# Notch-Filter-1.net
KiCad netlist of a schematic drawn in Altium Designer
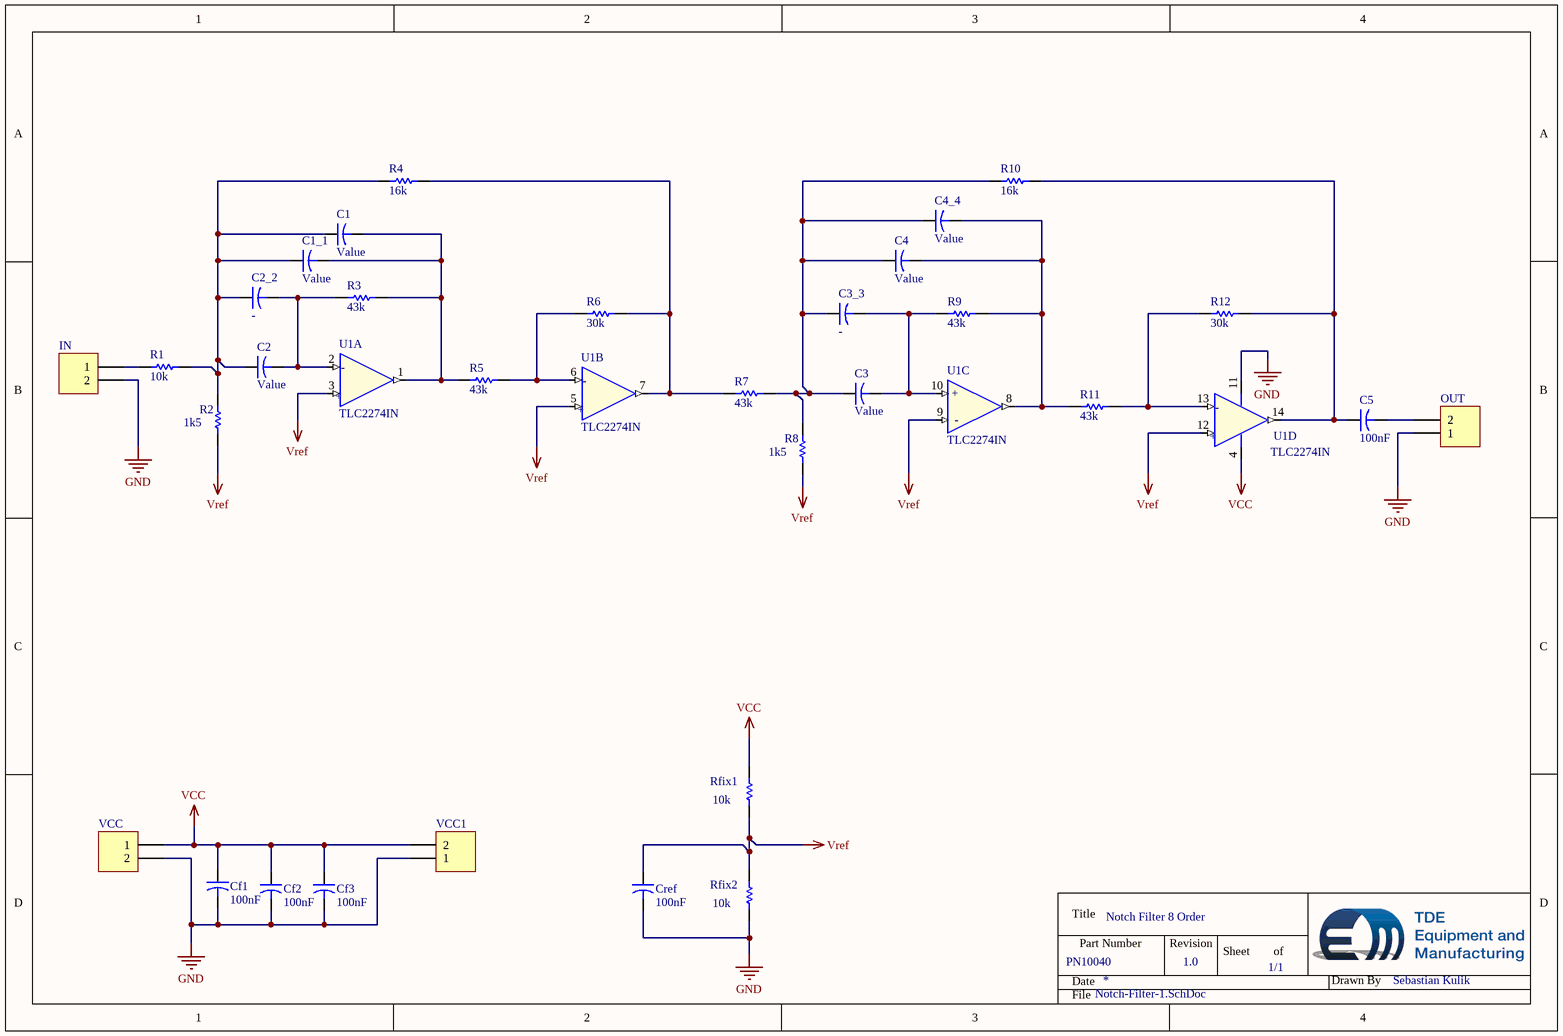
[diagram p0: Notch-Filter-1.SchDoc]

(export (version "E")
  (design (tool "Eeschema 10.0.6"))
  (components
    (comp (ref "C1")
      (value "Value")
      (footprint "Dummy-10mm")
      (description "Capacitor-Dummy-THT")
      (fields (field (name "PUBLISHER") "Sebastian Kulik"))
      (libsource (lib "Capacitors") (part "Capacitor-Dummy-THT"))
    )
    (comp (ref "C1_1")
      (value "Value")
      (footprint "Dummy-10mm")
      (description "Capacitor-Dummy-THT")
      (fields (field (name "PUBLISHER") "Sebastian Kulik"))
      (libsource (lib "Capacitors") (part "Capacitor-Dummy-THT"))
    )
    (comp (ref "C2")
      (value "Value")
      (footprint "Dummy-10mm")
      (description "Capacitor-Dummy-THT")
      (fields (field (name "PUBLISHER") "Sebastian Kulik"))
      (libsource (lib "Capacitors") (part "Capacitor-Dummy-THT"))
    )
    (comp (ref "C2_2")
      (value "-")
      (footprint "Dummy-10mm")
      (description "Capacitor-Dummy-THT")
      (fields (field (name "PUBLISHER") "Sebastian Kulik"))
      (libsource (lib "Capacitors") (part "Capacitor-Dummy-THT"))
    )
    (comp (ref "C3")
      (value "Value")
      (footprint "Dummy-10mm")
      (description "Capacitor-Dummy-THT")
      (fields (field (name "PUBLISHER") "Sebastian Kulik"))
      (libsource (lib "Capacitors") (part "Capacitor-Dummy-THT"))
    )
    (comp (ref "C3_3")
      (value "-")
      (footprint "Dummy-10mm")
      (description "Capacitor-Dummy-THT")
      (fields (field (name "PUBLISHER") "Sebastian Kulik"))
      (libsource (lib "Capacitors") (part "Capacitor-Dummy-THT"))
    )
    (comp (ref "C4")
      (value "Value")
      (footprint "Dummy-10mm")
      (description "Capacitor-Dummy-THT")
      (fields (field (name "PUBLISHER") "Sebastian Kulik"))
      (libsource (lib "Capacitors") (part "Capacitor-Dummy-THT"))
    )
    (comp (ref "C4_4")
      (value "Value")
      (footprint "Dummy-10mm")
      (description "Capacitor-Dummy-THT")
      (fields (field (name "PUBLISHER") "Sebastian Kulik"))
      (libsource (lib "Capacitors") (part "Capacitor-Dummy-THT"))
    )
    (comp (ref "C5")
      (value "100nF")
      (footprint "Dummy-10mm")
      (description "Capacitor-Dummy-THT")
      (fields (field (name "PUBLISHER") "Sebastian Kulik"))
      (libsource (lib "Capacitors") (part "Capacitor-Dummy-THT"))
    )
    (comp (ref "Cf1")
      (value "100nF")
      (footprint "Dummy-10mm")
      (description "Capacitor-Dummy-THT")
      (fields (field (name "PUBLISHER") "Sebastian Kulik"))
      (libsource (lib "Capacitors") (part "Capacitor-Dummy-THT"))
    )
    (comp (ref "Cf2")
      (value "100nF")
      (footprint "Dummy-10mm")
      (description "Capacitor-Dummy-THT")
      (fields (field (name "PUBLISHER") "Sebastian Kulik"))
      (libsource (lib "Capacitors") (part "Capacitor-Dummy-THT"))
    )
    (comp (ref "Cf3")
      (value "100nF")
      (footprint "Dummy-10mm")
      (description "Capacitor-Dummy-THT")
      (fields (field (name "PUBLISHER") "Sebastian Kulik"))
      (libsource (lib "Capacitors") (part "Capacitor-Dummy-THT"))
    )
    (comp (ref "Cref")
      (value "100nF")
      (footprint "Dummy-10mm")
      (description "Capacitor-Dummy-THT")
      (fields (field (name "PUBLISHER") "Sebastian Kulik"))
      (libsource (lib "Capacitors") (part "Capacitor-Dummy-THT"))
    )
    (comp (ref "IN")
      (value "PHOENIX_1715721")
      (footprint "Phoenix-2-5_08")
      (description "Phoenix, 2 pol, 5.08mm, 22A, 715721")
      (fields (field (name "MANUFACTURER") "Phoenix") (field (name "PUBLISHER") "Sebastian Kulik"))
      (libsource (lib "") (part "2Pol_1715721_1"))
    )
    (comp (ref "OUT")
      (value "PHOENIX_1715721")
      (footprint "Phoenix-2-5_08")
      (description "Phoenix, 2 pol, 5.08mm, 22A, 715721")
      (fields (field (name "MANUFACTURER") "Phoenix") (field (name "PUBLISHER") "Sebastian Kulik"))
      (libsource (lib "Connectors") (part "2Pol_1715721"))
    )
    (comp (ref "R1")
      (value "10k")
      (footprint "Dummy-10mm")
      (description "Resistor-Dummy-THT")
      (fields (field (name "PUBLISHER") "Sebastian Kulik"))
      (libsource (lib "Resistors") (part "Resistor-Dummy-THT"))
    )
    (comp (ref "R2")
      (value "1k5")
      (footprint "Dummy-10mm")
      (description "Resistor-Dummy-THT")
      (fields (field (name "PUBLISHER") "Sebastian Kulik"))
      (libsource (lib "Resistors") (part "Resistor-Dummy-THT"))
    )
    (comp (ref "R3")
      (value "43k")
      (footprint "Dummy-10mm")
      (description "Resistor-Dummy-THT")
      (fields (field (name "PUBLISHER") "Sebastian Kulik"))
      (libsource (lib "Resistors") (part "Resistor-Dummy-THT"))
    )
    (comp (ref "R4")
      (value "16k")
      (footprint "Dummy-10mm")
      (description "Resistor-Dummy-THT")
      (fields (field (name "PUBLISHER") "Sebastian Kulik"))
      (libsource (lib "Resistors") (part "Resistor-Dummy-THT"))
    )
    (comp (ref "R5")
      (value "43k")
      (footprint "Dummy-10mm")
      (description "Resistor-Dummy-THT")
      (fields (field (name "PUBLISHER") "Sebastian Kulik"))
      (libsource (lib "Resistors") (part "Resistor-Dummy-THT"))
    )
    (comp (ref "R6")
      (value "30k")
      (footprint "Dummy-10mm")
      (description "Resistor-Dummy-THT")
      (fields (field (name "PUBLISHER") "Sebastian Kulik"))
      (libsource (lib "Resistors") (part "Resistor-Dummy-THT"))
    )
    (comp (ref "R7")
      (value "43k")
      (footprint "Dummy-10mm")
      (description "Resistor-Dummy-THT")
      (fields (field (name "PUBLISHER") "Sebastian Kulik"))
      (libsource (lib "Resistors") (part "Resistor-Dummy-THT"))
    )
    (comp (ref "R8")
      (value "1k5")
      (footprint "Dummy-10mm")
      (description "Resistor-Dummy-THT")
      (fields (field (name "PUBLISHER") "Sebastian Kulik"))
      (libsource (lib "Resistors") (part "Resistor-Dummy-THT"))
    )
    (comp (ref "R9")
      (value "43k")
      (footprint "Dummy-10mm")
      (description "Resistor-Dummy-THT")
      (fields (field (name "PUBLISHER") "Sebastian Kulik"))
      (libsource (lib "Resistors") (part "Resistor-Dummy-THT"))
    )
    (comp (ref "R10")
      (value "16k")
      (footprint "Dummy-10mm")
      (description "Resistor-Dummy-THT")
      (fields (field (name "PUBLISHER") "Sebastian Kulik"))
      (libsource (lib "Resistors") (part "Resistor-Dummy-THT"))
    )
    (comp (ref "R11")
      (value "43k")
      (footprint "Dummy-10mm")
      (description "Resistor-Dummy-THT")
      (fields (field (name "PUBLISHER") "Sebastian Kulik"))
      (libsource (lib "Resistors") (part "Resistor-Dummy-THT"))
    )
    (comp (ref "R12")
      (value "30k")
      (footprint "Dummy-10mm")
      (description "Resistor-Dummy-THT")
      (fields (field (name "PUBLISHER") "Sebastian Kulik"))
      (libsource (lib "Resistors") (part "Resistor-Dummy-THT"))
    )
    (comp (ref "Rfix1")
      (value "10k")
      (footprint "Dummy-10mm")
      (description "Resistor-Dummy-THT")
      (fields (field (name "PUBLISHER") "Sebastian Kulik"))
      (libsource (lib "Resistors") (part "Resistor-Dummy-THT"))
    )
    (comp (ref "Rfix2")
      (value "10k")
      (footprint "Dummy-10mm")
      (description "Resistor-Dummy-THT")
      (fields (field (name "PUBLISHER") "Sebastian Kulik"))
      (libsource (lib "Resistors") (part "Resistor-Dummy-THT"))
    )
    (comp (ref "U1")
      (value "TLC2274IN")
      (footprint "DIP-14")
      (description "Reel to Reel  quad OP")
      (fields (field (name "MANUFACTURER") "TI") (field (name "PUBLISHER") "Sebastian Kulik"))
      (libsource (lib "ICs") (part "TLC2274IN"))
    )
    (comp (ref "VCC")
      (value "PHOENIX_1715721")
      (footprint "Phoenix-2-5_08")
      (description "Phoenix, 2 pol, 5.08mm, 22A, 715721")
      (fields (field (name "MANUFACTURER") "Phoenix") (field (name "PUBLISHER") "Sebastian Kulik"))
      (libsource (lib "") (part "2Pol_1715721_1"))
    )
    (comp (ref "VCC1")
      (value "PHOENIX_1715721")
      (footprint "Phoenix-2-5_08")
      (description "Phoenix, 2 pol, 5.08mm, 22A, 715721")
      (fields (field (name "MANUFACTURER") "Phoenix") (field (name "PUBLISHER") "Sebastian Kulik"))
      (libsource (lib "Connectors") (part "2Pol_1715721"))
    )
  )
  (nets
    (net (code "1") (name "GND") (class "Default")
      (node (ref "Cf1") (pin "2") (pinfunction "2_2") (pintype "passive"))
      (node (ref "Cf2") (pin "2") (pinfunction "2_2") (pintype "passive"))
      (node (ref "Cf3") (pin "2") (pinfunction "2_2") (pintype "passive"))
      (node (ref "Cref") (pin "2") (pinfunction "2_2") (pintype "passive"))
      (node (ref "IN") (pin "2") (pinfunction "2_2") (pintype "passive"))
      (node (ref "OUT") (pin "1") (pinfunction "1_1") (pintype "passive"))
      (node (ref "Rfix2") (pin "1") (pinfunction "1_1") (pintype "passive"))
      (node (ref "U1") (pin "11") (pinfunction "V-_11") (pintype "power_in"))
      (node (ref "VCC") (pin "2") (pinfunction "2_2") (pintype "passive"))
      (node (ref "VCC1") (pin "1") (pinfunction "1_1") (pintype "passive"))
    )
    (net (code "2") (name "Net-(C1-Pad1)") (class "Default")
      (node (ref "C1") (pin "1") (pinfunction "1_1") (pintype "passive"))
      (node (ref "C1_1") (pin "1") (pinfunction "1_1") (pintype "passive"))
      (node (ref "C2") (pin "1") (pinfunction "1_1") (pintype "passive"))
      (node (ref "C2_2") (pin "1") (pinfunction "1_1") (pintype "passive"))
      (node (ref "R1") (pin "1") (pinfunction "1_1") (pintype "passive"))
      (node (ref "R2") (pin "2") (pinfunction "2_2") (pintype "passive"))
      (node (ref "R4") (pin "2") (pinfunction "2_2") (pintype "passive"))
    )
    (net (code "3") (name "Net-(C3-Pad1)") (class "Default")
      (node (ref "C3") (pin "1") (pinfunction "1_1") (pintype "passive"))
      (node (ref "C3_3") (pin "1") (pinfunction "1_1") (pintype "passive"))
      (node (ref "C4") (pin "1") (pinfunction "1_1") (pintype "passive"))
      (node (ref "C4_4") (pin "1") (pinfunction "1_1") (pintype "passive"))
      (node (ref "R10") (pin "2") (pinfunction "2_2") (pintype "passive"))
      (node (ref "R7") (pin "1") (pinfunction "1_1") (pintype "passive"))
      (node (ref "R8") (pin "2") (pinfunction "2_2") (pintype "passive"))
    )
    (net (code "4") (name "Net-(C5-Pad2)") (class "Default")
      (node (ref "C5") (pin "2") (pinfunction "2_2") (pintype "passive"))
      (node (ref "OUT") (pin "2") (pinfunction "2_2") (pintype "passive"))
    )
    (net (code "5") (name "Net-(IN-Pad1)") (class "Default")
      (node (ref "IN") (pin "1") (pinfunction "1_1") (pintype "passive"))
      (node (ref "R1") (pin "2") (pinfunction "2_2") (pintype "passive"))
    )
    (net (code "6") (name "Net-(U1A-IN+)") (class "Default")
      (node (ref "C2") (pin "2") (pinfunction "2_2") (pintype "passive"))
      (node (ref "C2_2") (pin "2") (pinfunction "2_2") (pintype "passive"))
      (node (ref "R3") (pin "1") (pinfunction "1_1") (pintype "passive"))
      (node (ref "U1") (pin "2") (pinfunction "IN+_2") (pintype "input"))
    )
    (net (code "7") (name "Net-(U1A-OUT)") (class "Default")
      (node (ref "C1") (pin "2") (pinfunction "2_2") (pintype "passive"))
      (node (ref "C1_1") (pin "2") (pinfunction "2_2") (pintype "passive"))
      (node (ref "R3") (pin "2") (pinfunction "2_2") (pintype "passive"))
      (node (ref "R5") (pin "1") (pinfunction "1_1") (pintype "passive"))
      (node (ref "U1") (pin "1") (pinfunction "OUT_1") (pintype "output"))
    )
    (net (code "8") (name "Net-(U1B-IN+)") (class "Default")
      (node (ref "R5") (pin "2") (pinfunction "2_2") (pintype "passive"))
      (node (ref "R6") (pin "1") (pinfunction "1_1") (pintype "passive"))
      (node (ref "U1") (pin "6") (pinfunction "IN+_6") (pintype "input"))
    )
    (net (code "9") (name "Net-(U1B-OUT)") (class "Default")
      (node (ref "R4") (pin "1") (pinfunction "1_1") (pintype "passive"))
      (node (ref "R6") (pin "2") (pinfunction "2_2") (pintype "passive"))
      (node (ref "R7") (pin "2") (pinfunction "2_2") (pintype "passive"))
      (node (ref "U1") (pin "7") (pinfunction "OUT_7") (pintype "output"))
    )
    (net (code "10") (name "Net-(U1C-IN-)") (class "Default")
      (node (ref "C3") (pin "2") (pinfunction "2_2") (pintype "passive"))
      (node (ref "C3_3") (pin "2") (pinfunction "2_2") (pintype "passive"))
      (node (ref "R9") (pin "2") (pinfunction "2_2") (pintype "passive"))
      (node (ref "U1") (pin "10") (pinfunction "IN-_10") (pintype "input"))
    )
    (net (code "11") (name "Net-(U1C-OUT)") (class "Default")
      (node (ref "C4") (pin "2") (pinfunction "2_2") (pintype "passive"))
      (node (ref "C4_4") (pin "2") (pinfunction "2_2") (pintype "passive"))
      (node (ref "R11") (pin "2") (pinfunction "2_2") (pintype "passive"))
      (node (ref "R9") (pin "1") (pinfunction "1_1") (pintype "passive"))
      (node (ref "U1") (pin "8") (pinfunction "OUT_8") (pintype "output"))
    )
    (net (code "12") (name "Net-(U1D-IN+)") (class "Default")
      (node (ref "R11") (pin "1") (pinfunction "1_1") (pintype "passive"))
      (node (ref "R12") (pin "2") (pinfunction "2_2") (pintype "passive"))
      (node (ref "U1") (pin "13") (pinfunction "IN+_13") (pintype "input"))
    )
    (net (code "13") (name "Net-(U1D-OUT)") (class "Default")
      (node (ref "C5") (pin "1") (pinfunction "1_1") (pintype "passive"))
      (node (ref "R10") (pin "1") (pinfunction "1_1") (pintype "passive"))
      (node (ref "R12") (pin "1") (pinfunction "1_1") (pintype "passive"))
      (node (ref "U1") (pin "14") (pinfunction "OUT_14") (pintype "output"))
    )
    (net (code "14") (name "VCC") (class "Default")
      (node (ref "Cf1") (pin "1") (pinfunction "1_1") (pintype "passive"))
      (node (ref "Cf2") (pin "1") (pinfunction "1_1") (pintype "passive"))
      (node (ref "Cf3") (pin "1") (pinfunction "1_1") (pintype "passive"))
      (node (ref "Rfix1") (pin "2") (pinfunction "2_2") (pintype "passive"))
      (node (ref "U1") (pin "4") (pinfunction "V+_4") (pintype "power_in"))
      (node (ref "VCC") (pin "1") (pinfunction "1_1") (pintype "passive"))
      (node (ref "VCC1") (pin "2") (pinfunction "2_2") (pintype "passive"))
    )
    (net (code "15") (name "Vref") (class "Default")
      (node (ref "Cref") (pin "1") (pinfunction "1_1") (pintype "passive"))
      (node (ref "R2") (pin "1") (pinfunction "1_1") (pintype "passive"))
      (node (ref "R8") (pin "1") (pinfunction "1_1") (pintype "passive"))
      (node (ref "Rfix1") (pin "1") (pinfunction "1_1") (pintype "passive"))
      (node (ref "Rfix2") (pin "2") (pinfunction "2_2") (pintype "passive"))
      (node (ref "U1") (pin "12") (pinfunction "IN-_12") (pintype "input"))
      (node (ref "U1") (pin "3") (pinfunction "IN-_3") (pintype "input"))
      (node (ref "U1") (pin "5") (pinfunction "IN-_5") (pintype "input"))
      (node (ref "U1") (pin "9") (pinfunction "IN+_9") (pintype "input"))
    )
  )
)
